# altair_sch.net
KiCad netlist of a schematic drawn in EAGLE
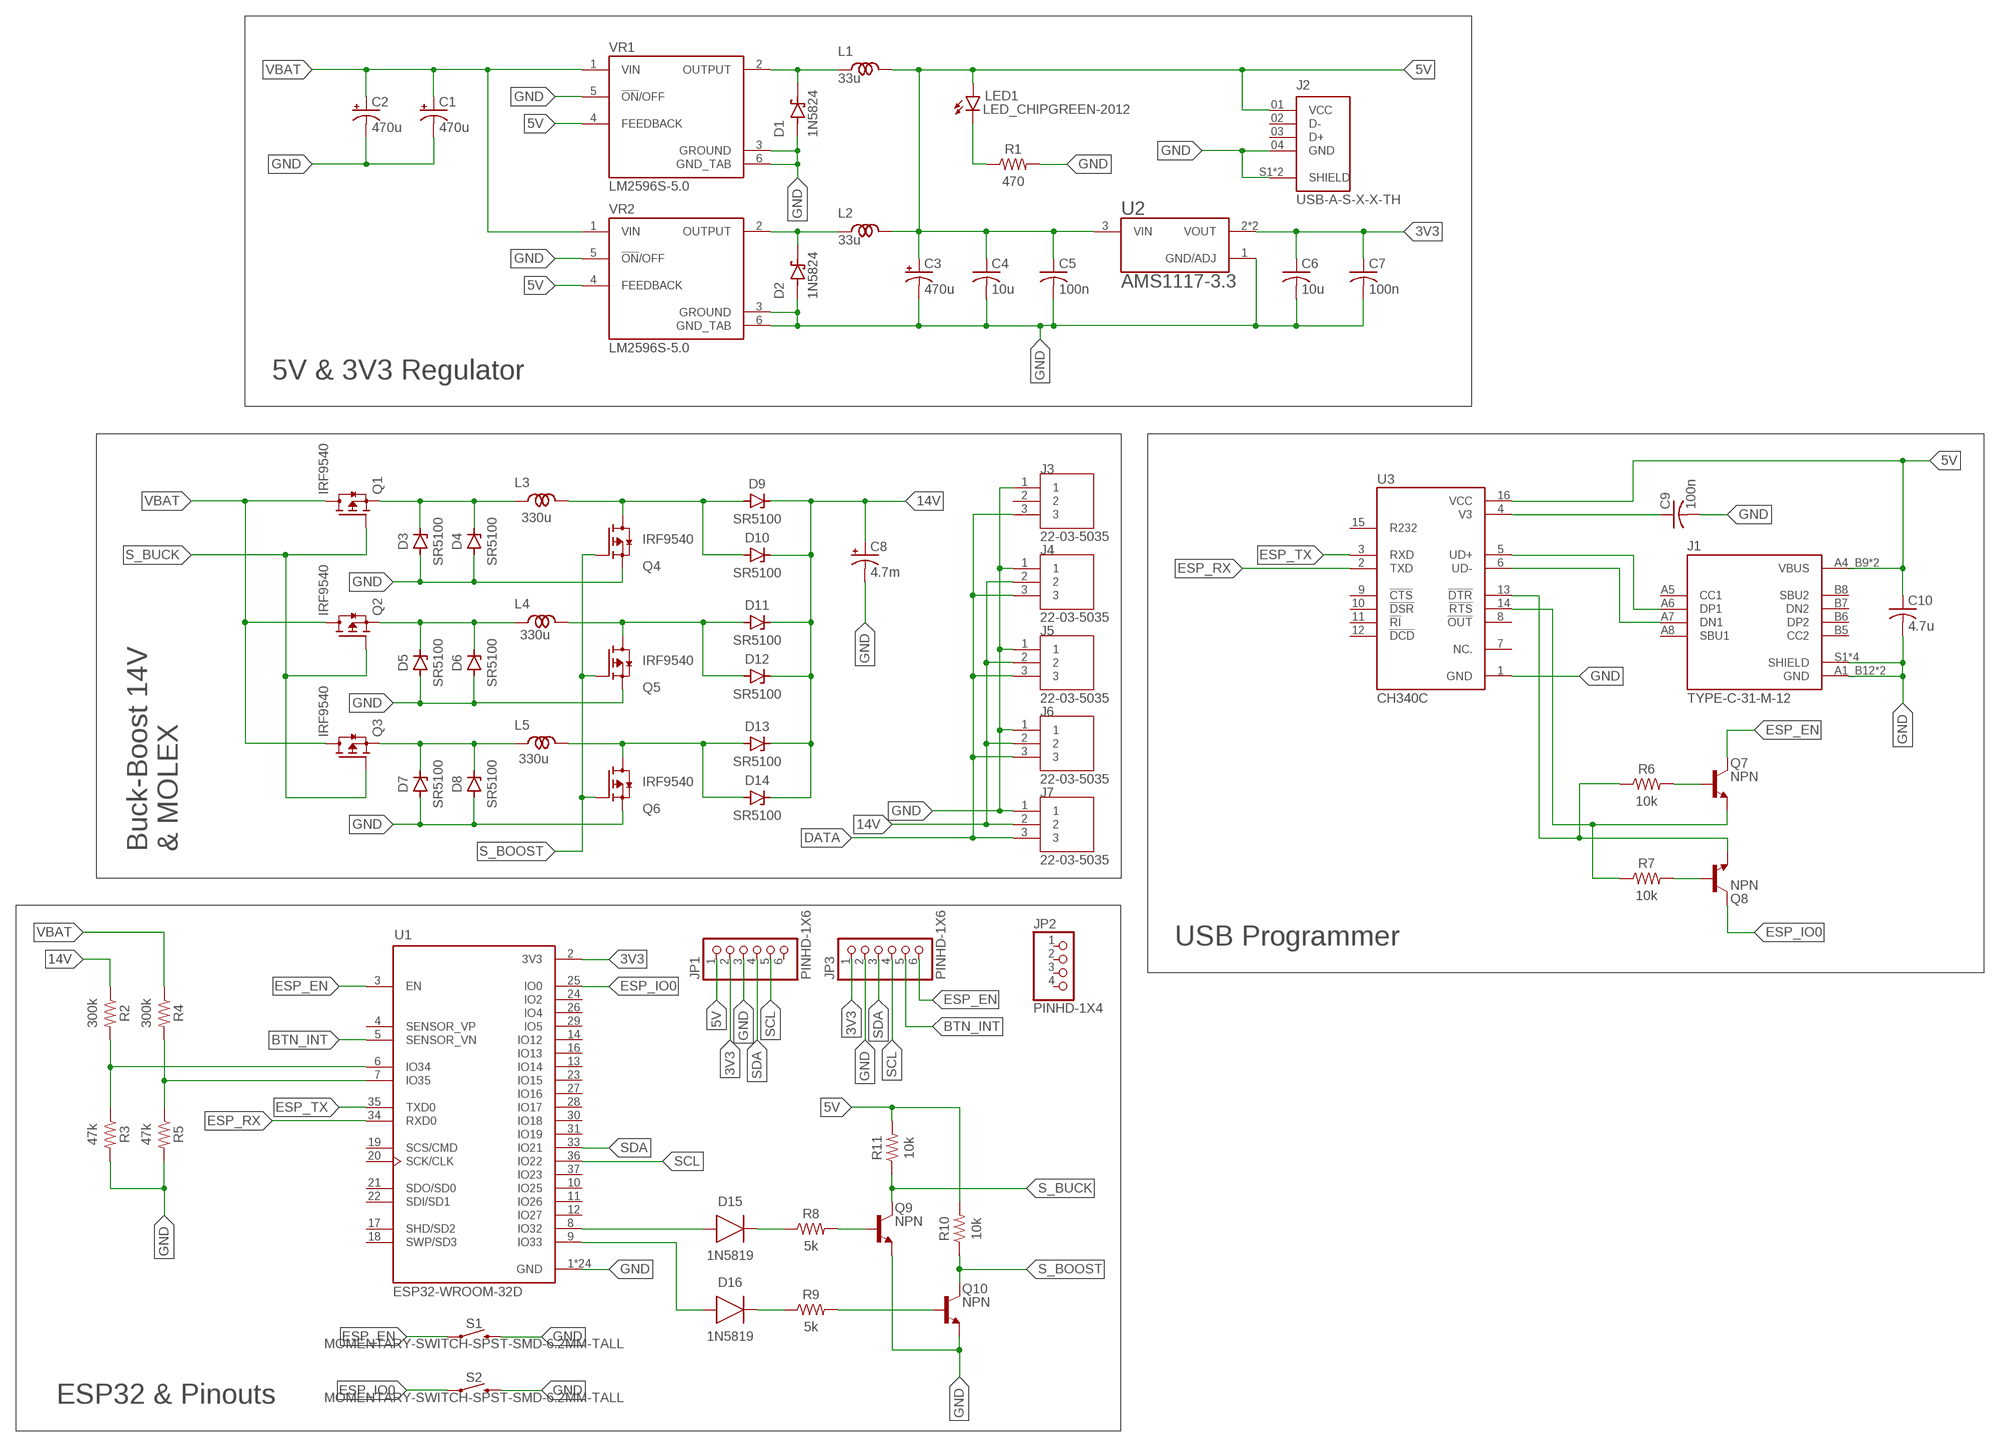
[diagram p0: schematic, sheet 1]

(export (version "E")
  (design (tool "Eeschema 10.0.6"))
  (components
    (comp (ref "C1")
      (value "470u")
      (footprint "eagle-import:CAPAE1030X1050N")
      (libsource (lib "eagle-import") (part "C-POL-USECAP-10.5MM_"))
    )
    (comp (ref "C2")
      (value "470u")
      (footprint "eagle-import:CAPAE1030X1050N")
      (libsource (lib "eagle-import") (part "C-POL-USECAP-10.5MM_"))
    )
    (comp (ref "C3")
      (value "470u")
      (footprint "eagle-import:CAPAE1030X1050N")
      (libsource (lib "eagle-import") (part "C-POL-USECAP-10.5MM_"))
    )
    (comp (ref "C4")
      (value "10u")
      (footprint "eagle-import:CAPC2012X110")
      (libsource (lib "eagle-import") (part "C-USCHIP-0805(2012-METRIC)_"))
    )
    (comp (ref "C5")
      (value "100n")
      (footprint "eagle-import:CAPC2012X110")
      (libsource (lib "eagle-import") (part "C-USCHIP-0805(2012-METRIC)_"))
    )
    (comp (ref "C6")
      (value "10u")
      (footprint "eagle-import:CAPC2012X110")
      (libsource (lib "eagle-import") (part "C-USCHIP-0805(2012-METRIC)_"))
    )
    (comp (ref "C7")
      (value "100n")
      (footprint "eagle-import:CAPC2012X110")
      (libsource (lib "eagle-import") (part "C-USCHIP-0805(2012-METRIC)_"))
    )
    (comp (ref "C8")
      (value "4.7m")
      (footprint "eagle-import:CAPPRD550W60D1200H2000B")
      (libsource (lib "eagle-import") (part "C-POL-USRADIAL-20MM-DIA_"))
    )
    (comp (ref "C9")
      (value "100n")
      (footprint "eagle-import:CAPC2012X110")
      (libsource (lib "eagle-import") (part "C-USCHIP-0805(2012-METRIC)_"))
    )
    (comp (ref "C10")
      (value "4.7u")
      (footprint "eagle-import:CAPC2012X110")
      (libsource (lib "eagle-import") (part "C-USCHIP-0805(2012-METRIC)_"))
    )
    (comp (ref "D1")
      (value "1N5824")
      (footprint "eagle-import:SODFL4725X110N")
      (fields (field (name "MF") "Taiwan Semiconductor") (field (name "MP") "SS54FSH"))
      (libsource (lib "eagle-import") (part "SS54FSH"))
    )
    (comp (ref "D2")
      (value "1N5824")
      (footprint "eagle-import:SODFL4725X110N")
      (fields (field (name "MF") "Taiwan Semiconductor") (field (name "MP") "SS54FSH"))
      (libsource (lib "eagle-import") (part "SS54FSH"))
    )
    (comp (ref "D3")
      (value "SR5100")
      (footprint "eagle-import:DIOM5226X290N")
      (libsource (lib "eagle-import") (part "ZENERDO-214AC(SMA)"))
    )
    (comp (ref "D4")
      (value "SR5100")
      (footprint "eagle-import:DIOM5226X290N")
      (libsource (lib "eagle-import") (part "ZENERDO-214AC(SMA)"))
    )
    (comp (ref "D5")
      (value "SR5100")
      (footprint "eagle-import:DIOM5226X290N")
      (libsource (lib "eagle-import") (part "ZENERDO-214AC(SMA)"))
    )
    (comp (ref "D6")
      (value "SR5100")
      (footprint "eagle-import:DIOM5226X290N")
      (libsource (lib "eagle-import") (part "ZENERDO-214AC(SMA)"))
    )
    (comp (ref "D7")
      (value "SR5100")
      (footprint "eagle-import:DIOM5226X290N")
      (libsource (lib "eagle-import") (part "ZENERDO-214AC(SMA)"))
    )
    (comp (ref "D8")
      (value "SR5100")
      (footprint "eagle-import:DIOM5226X290N")
      (libsource (lib "eagle-import") (part "ZENERDO-214AC(SMA)"))
    )
    (comp (ref "D9")
      (value "SR5100")
      (footprint "eagle-import:DIOM5226X290N")
      (libsource (lib "eagle-import") (part "ZENERDO-214AC(SMA)"))
    )
    (comp (ref "D10")
      (value "SR5100")
      (footprint "eagle-import:DIOM5226X290N")
      (libsource (lib "eagle-import") (part "ZENERDO-214AC(SMA)"))
    )
    (comp (ref "D11")
      (value "SR5100")
      (footprint "eagle-import:DIOM5226X290N")
      (libsource (lib "eagle-import") (part "ZENERDO-214AC(SMA)"))
    )
    (comp (ref "D12")
      (value "SR5100")
      (footprint "eagle-import:DIOM5226X290N")
      (libsource (lib "eagle-import") (part "ZENERDO-214AC(SMA)"))
    )
    (comp (ref "D13")
      (value "SR5100")
      (footprint "eagle-import:DIOM5226X290N")
      (libsource (lib "eagle-import") (part "ZENERDO-214AC(SMA)"))
    )
    (comp (ref "D14")
      (value "SR5100")
      (footprint "eagle-import:DIOM5226X290N")
      (libsource (lib "eagle-import") (part "ZENERDO-214AC(SMA)"))
    )
    (comp (ref "D15")
      (value "1N5819")
      (footprint "eagle-import:DIOM5226X290N")
      (libsource (lib "eagle-import") (part "DIODEDO-214AC(SMA)"))
    )
    (comp (ref "D16")
      (value "1N5819")
      (footprint "eagle-import:DIOM5226X290N")
      (libsource (lib "eagle-import") (part "DIODEDO-214AC(SMA)"))
    )
    (comp (ref "J1")
      (value "TYPE-C-31-M-12")
      (footprint "eagle-import:HRO_TYPE-C-31-M-12")
      (fields (field (name "MF") "HRO Electronics Co., Ltd."))
      (libsource (lib "eagle-import") (part "TYPE-C-31-M-12"))
    )
    (comp (ref "J2")
      (value "USB-A-S-X-X-TH")
      (footprint "eagle-import:SAMTEC_USB-A-S-X-X-TH")
      (fields (field (name "MF") "Samtec") (field (name "MP") "USB-A-S-S-W-TH"))
      (libsource (lib "eagle-import") (part "USB-A-S-X-X-TH"))
    )
    (comp (ref "J3")
      (value "22-03-5035")
      (footprint "eagle-import:MOLEX_22-03-5035")
      (fields (field (name "MF") "Molex"))
      (libsource (lib "eagle-import") (part "22-03-5035"))
    )
    (comp (ref "J4")
      (value "22-03-5035")
      (footprint "eagle-import:MOLEX_22-03-5035")
      (fields (field (name "MF") "Molex"))
      (libsource (lib "eagle-import") (part "22-03-5035"))
    )
    (comp (ref "J5")
      (value "22-03-5035")
      (footprint "eagle-import:MOLEX_22-03-5035")
      (fields (field (name "MF") "Molex"))
      (libsource (lib "eagle-import") (part "22-03-5035"))
    )
    (comp (ref "J6")
      (value "22-03-5035")
      (footprint "eagle-import:MOLEX_22-03-5035")
      (fields (field (name "MF") "Molex"))
      (libsource (lib "eagle-import") (part "22-03-5035"))
    )
    (comp (ref "J7")
      (value "22-03-5035")
      (footprint "eagle-import:MOLEX_22-03-5035")
      (fields (field (name "MF") "Molex"))
      (libsource (lib "eagle-import") (part "22-03-5035"))
    )
    (comp (ref "JP1")
      (value "PINHD-1X6")
      (footprint "eagle-import:1X06")
      (fields (field (name "MANUFACTURER") "Generic"))
      (libsource (lib "eagle-import") (part "PINHD-1X6"))
    )
    (comp (ref "JP2")
      (value "PINHD-1X4")
      (footprint "eagle-import:1X04")
      (fields (field (name "MANUFACTURER") "Generic"))
      (libsource (lib "eagle-import") (part "PINHD-1X4"))
    )
    (comp (ref "JP3")
      (value "PINHD-1X6")
      (footprint "eagle-import:1X06")
      (fields (field (name "MANUFACTURER") "Generic"))
      (libsource (lib "eagle-import") (part "PINHD-1X6"))
    )
    (comp (ref "L1")
      (value "33u")
      (footprint "eagle-import:CDRH127R")
      (libsource (lib "eagle-import") (part "CDRH127R"))
    )
    (comp (ref "L2")
      (value "33u")
      (footprint "eagle-import:CDRH127R")
      (libsource (lib "eagle-import") (part "CDRH127R"))
    )
    (comp (ref "L3")
      (value "330u")
      (footprint "eagle-import:CDRH127R")
      (libsource (lib "eagle-import") (part "CDRH127R"))
    )
    (comp (ref "L4")
      (value "330u")
      (footprint "eagle-import:CDRH127R")
      (libsource (lib "eagle-import") (part "CDRH127R"))
    )
    (comp (ref "L5")
      (value "330u")
      (footprint "eagle-import:CDRH127R")
      (libsource (lib "eagle-import") (part "CDRH127R"))
    )
    (comp (ref "LED1")
      (value "LED_CHIPGREEN-2012")
      (footprint "eagle-import:LEDC2012X110N_G")
      (libsource (lib "eagle-import") (part "LED_CHIPGREEN-2012"))
    )
    (comp (ref "Q1")
      (value "IRF9540")
      (footprint "eagle-import:TO254P1052X465X1989-3")
      (fields (field (name "MF") "Vishay Siliconix"))
      (libsource (lib "eagle-import") (part "IRF9540"))
    )
    (comp (ref "Q2")
      (value "IRF9540")
      (footprint "eagle-import:TO254P1052X465X1989-3")
      (fields (field (name "MF") "Vishay Siliconix"))
      (libsource (lib "eagle-import") (part "IRF9540"))
    )
    (comp (ref "Q3")
      (value "IRF9540")
      (footprint "eagle-import:TO254P1052X465X1989-3")
      (fields (field (name "MF") "Vishay Siliconix"))
      (libsource (lib "eagle-import") (part "IRF9540"))
    )
    (comp (ref "Q4")
      (value "IRF9540")
      (footprint "eagle-import:TO254P1052X465X1989-3")
      (fields (field (name "MF") "Vishay Siliconix"))
      (libsource (lib "eagle-import") (part "IRF9540"))
    )
    (comp (ref "Q5")
      (value "IRF9540")
      (footprint "eagle-import:TO254P1052X465X1989-3")
      (fields (field (name "MF") "Vishay Siliconix"))
      (libsource (lib "eagle-import") (part "IRF9540"))
    )
    (comp (ref "Q6")
      (value "IRF9540")
      (footprint "eagle-import:TO254P1052X465X1989-3")
      (fields (field (name "MF") "Vishay Siliconix"))
      (libsource (lib "eagle-import") (part "IRF9540"))
    )
    (comp (ref "Q7")
      (value "NPN")
      (footprint "eagle-import:SOT95P237X112-3N")
      (libsource (lib "eagle-import") (part "NPNSOT23-BEC_"))
    )
    (comp (ref "Q8")
      (value "NPN")
      (footprint "eagle-import:SOT95P237X112-3N")
      (libsource (lib "eagle-import") (part "NPNSOT23-BEC_"))
    )
    (comp (ref "Q9")
      (value "NPN")
      (footprint "eagle-import:SOT95P237X112-3N")
      (libsource (lib "eagle-import") (part "NPNSOT23-BEC_"))
    )
    (comp (ref "Q10")
      (value "NPN")
      (footprint "eagle-import:SOT95P237X112-3N")
      (libsource (lib "eagle-import") (part "NPNSOT23-BEC_"))
    )
    (comp (ref "R1")
      (value "470")
      (footprint "eagle-import:RESC2012X65")
      (libsource (lib "eagle-import") (part "R-USCHIP-0805(2012-METRIC)_"))
    )
    (comp (ref "R2")
      (value "300k")
      (footprint "eagle-import:RESC2012X65")
      (libsource (lib "eagle-import") (part "R-USCHIP-0805(2012-METRIC)_"))
    )
    (comp (ref "R3")
      (value "47k")
      (footprint "eagle-import:RESC2012X65")
      (libsource (lib "eagle-import") (part "R-USCHIP-0805(2012-METRIC)_"))
    )
    (comp (ref "R4")
      (value "300k")
      (footprint "eagle-import:RESC2012X65")
      (libsource (lib "eagle-import") (part "R-USCHIP-0805(2012-METRIC)_"))
    )
    (comp (ref "R5")
      (value "47k")
      (footprint "eagle-import:RESC2012X65")
      (libsource (lib "eagle-import") (part "R-USCHIP-0805(2012-METRIC)_"))
    )
    (comp (ref "R6")
      (value "10k")
      (footprint "eagle-import:RESC2012X65")
      (libsource (lib "eagle-import") (part "R-USCHIP-0805(2012-METRIC)_"))
    )
    (comp (ref "R7")
      (value "10k")
      (footprint "eagle-import:RESC2012X65")
      (libsource (lib "eagle-import") (part "R-USCHIP-0805(2012-METRIC)_"))
    )
    (comp (ref "R8")
      (value "5k")
      (footprint "eagle-import:RESC2012X65")
      (libsource (lib "eagle-import") (part "R-USCHIP-0805(2012-METRIC)_"))
    )
    (comp (ref "R9")
      (value "5k")
      (footprint "eagle-import:RESC2012X65")
      (libsource (lib "eagle-import") (part "R-USCHIP-0805(2012-METRIC)_"))
    )
    (comp (ref "R10")
      (value "10k")
      (footprint "eagle-import:RESC2012X65")
      (libsource (lib "eagle-import") (part "R-USCHIP-0805(2012-METRIC)_"))
    )
    (comp (ref "R11")
      (value "10k")
      (footprint "eagle-import:RESC2012X65")
      (libsource (lib "eagle-import") (part "R-USCHIP-0805(2012-METRIC)_"))
    )
    (comp (ref "S1")
      (value "MOMENTARY-SWITCH-SPST-SMD-6.2MM-TALL")
      (footprint "eagle-import:TACTILE_SWITCH_SMD_6.2MM_TALL")
      (libsource (lib "eagle-import") (part "MOMENTARY-SWITCH-SPST-SMD-6.2MM-TALL"))
    )
    (comp (ref "S2")
      (value "MOMENTARY-SWITCH-SPST-SMD-6.2MM-TALL")
      (footprint "eagle-import:TACTILE_SWITCH_SMD_6.2MM_TALL")
      (libsource (lib "eagle-import") (part "MOMENTARY-SWITCH-SPST-SMD-6.2MM-TALL"))
    )
    (comp (ref "U1")
      (value "ESP32-WROOM-32D")
      (footprint "eagle-import:MODULE_ESP32-WROOM-32D")
      (fields (field (name "MF") "Espressif Systems"))
      (libsource (lib "eagle-import") (part "ESP32-WROOM-32D"))
    )
    (comp (ref "U2")
      (value "AMS1117-3.3")
      (footprint "eagle-import:SOT229P700X180-4N")
      (fields (field (name "MF") "Advanced Monolithic Systems"))
      (libsource (lib "eagle-import") (part "AMS1117-3.3"))
    )
    (comp (ref "U3")
      (value "CH340C")
      (footprint "eagle-import:SOIC127P600X180-16N")
      (fields (field (name "MF") "WCH"))
      (libsource (lib "eagle-import") (part "CH340C"))
    )
    (comp (ref "VR1")
      (value "LM2596S-5.0")
      (footprint "eagle-import:TO170P1524X483-6N")
      (fields (field (name "MF") "Texas Instruments") (field (name "MP") "LM2596S-5.0/NOPB"))
      (libsource (lib "eagle-import") (part "LM2596S-5.0"))
    )
    (comp (ref "VR2")
      (value "LM2596S-5.0")
      (footprint "eagle-import:TO170P1524X483-6N")
      (fields (field (name "MF") "Texas Instruments") (field (name "MP") "LM2596S-5.0/NOPB"))
      (libsource (lib "eagle-import") (part "LM2596S-5.0"))
    )
  )
  (nets
    (net (code "1") (name "3V3") (class "Default")
      (node (ref "C6") (pin "1") (pinfunction "1_1") (pintype "passive"))
      (node (ref "C7") (pin "1") (pinfunction "1_1") (pintype "passive"))
      (node (ref "JP1") (pin "2") (pinfunction "2_2") (pintype "passive"))
      (node (ref "JP3") (pin "1") (pinfunction "1_1") (pintype "passive"))
      (node (ref "U1") (pin "2") (pinfunction "3V3_2") (pintype "power_in"))
      (node (ref "U2") (pin "2") (pinfunction "VOUT_2") (pintype "output"))
      (node (ref "U2") (pin "4") (pinfunction "VOUT_4") (pintype "output"))
    )
    (net (code "2") (name "5V") (class "Default")
      (node (ref "C10") (pin "1") (pinfunction "1_1") (pintype "passive"))
      (node (ref "C3") (pin "1") (pinfunction "+_1") (pintype "passive"))
      (node (ref "C4") (pin "1") (pinfunction "1_1") (pintype "passive"))
      (node (ref "C5") (pin "1") (pinfunction "1_1") (pintype "passive"))
      (node (ref "J1") (pin "A4_B9") (pinfunction "VBUS_A4_B9") (pintype "power_in"))
      (node (ref "J1") (pin "B4_A9") (pinfunction "VBUS_B4_A9") (pintype "power_in"))
      (node (ref "J2") (pin "01") (pinfunction "VCC_01") (pintype "power_in"))
      (node (ref "JP1") (pin "1") (pinfunction "1_1") (pintype "passive"))
      (node (ref "L1") (pin "P$2") (pinfunction "P$2_P$2") (pintype "bidirectional"))
      (node (ref "L2") (pin "P$2") (pinfunction "P$2_P$2") (pintype "bidirectional"))
      (node (ref "LED1") (pin "2") (pinfunction "A_2") (pintype "passive"))
      (node (ref "R10") (pin "2") (pinfunction "2_2") (pintype "passive"))
      (node (ref "R11") (pin "2") (pinfunction "2_2") (pintype "passive"))
      (node (ref "U2") (pin "3") (pinfunction "VIN_3") (pintype "input"))
      (node (ref "U3") (pin "16") (pinfunction "VCC_16") (pintype "power_in"))
      (node (ref "VR1") (pin "4") (pinfunction "FEEDBACK_4") (pintype "input"))
      (node (ref "VR2") (pin "4") (pinfunction "FEEDBACK_4") (pintype "input"))
    )
    (net (code "3") (name "14V") (class "Default")
      (node (ref "C8") (pin "1") (pinfunction "+_1") (pintype "passive"))
      (node (ref "D10") (pin "1") (pinfunction "C_1") (pintype "passive"))
      (node (ref "D11") (pin "1") (pinfunction "C_1") (pintype "passive"))
      (node (ref "D12") (pin "1") (pinfunction "C_1") (pintype "passive"))
      (node (ref "D13") (pin "1") (pinfunction "C_1") (pintype "passive"))
      (node (ref "D14") (pin "1") (pinfunction "C_1") (pintype "passive"))
      (node (ref "D9") (pin "1") (pinfunction "C_1") (pintype "passive"))
      (node (ref "J4") (pin "2") (pinfunction "2_2") (pintype "passive"))
      (node (ref "J5") (pin "2") (pinfunction "2_2") (pintype "passive"))
      (node (ref "J6") (pin "2") (pinfunction "2_2") (pintype "passive"))
      (node (ref "J7") (pin "2") (pinfunction "2_2") (pintype "passive"))
      (node (ref "R2") (pin "1") (pinfunction "1_1") (pintype "passive"))
    )
    (net (code "4") (name "BTN_INT") (class "Default")
      (node (ref "JP3") (pin "5") (pinfunction "5_5") (pintype "passive"))
      (node (ref "U1") (pin "5") (pinfunction "SENSOR_VN_5") (pintype "input"))
    )
    (net (code "5") (name "DATA") (class "Default")
      (node (ref "J3") (pin "3") (pinfunction "3_3") (pintype "passive"))
      (node (ref "J4") (pin "3") (pinfunction "3_3") (pintype "passive"))
      (node (ref "J5") (pin "3") (pinfunction "3_3") (pintype "passive"))
      (node (ref "J6") (pin "3") (pinfunction "3_3") (pintype "passive"))
      (node (ref "J7") (pin "3") (pinfunction "3_3") (pintype "passive"))
    )
    (net (code "6") (name "ESP_EN") (class "Default")
      (node (ref "JP3") (pin "6") (pinfunction "6_6") (pintype "passive"))
      (node (ref "Q7") (pin "3") (pinfunction "C_3") (pintype "passive"))
      (node (ref "S1") (pin "A2") (pinfunction "1_A2") (pintype "passive"))
      (node (ref "U1") (pin "3") (pinfunction "EN_3") (pintype "input"))
    )
    (net (code "7") (name "ESP_IO0") (class "Default")
      (node (ref "Q8") (pin "3") (pinfunction "C_3") (pintype "passive"))
      (node (ref "S2") (pin "A2") (pinfunction "1_A2") (pintype "passive"))
      (node (ref "U1") (pin "25") (pinfunction "IO0_25") (pintype "bidirectional"))
    )
    (net (code "8") (name "ESP_RX") (class "Default")
      (node (ref "U1") (pin "34") (pinfunction "RXD0_34") (pintype "bidirectional"))
      (node (ref "U3") (pin "2") (pinfunction "TXD_2") (pintype "output"))
    )
    (net (code "9") (name "ESP_TX") (class "Default")
      (node (ref "U1") (pin "35") (pinfunction "TXD0_35") (pintype "bidirectional"))
      (node (ref "U3") (pin "3") (pinfunction "RXD_3") (pintype "input"))
    )
    (net (code "10") (name "GND") (class "Default")
      (node (ref "C1") (pin "2") (pinfunction "-_2") (pintype "passive"))
      (node (ref "C10") (pin "2") (pinfunction "2_2") (pintype "passive"))
      (node (ref "C2") (pin "2") (pinfunction "-_2") (pintype "passive"))
      (node (ref "C3") (pin "2") (pinfunction "-_2") (pintype "passive"))
      (node (ref "C4") (pin "2") (pinfunction "2_2") (pintype "passive"))
      (node (ref "C5") (pin "2") (pinfunction "2_2") (pintype "passive"))
      (node (ref "C6") (pin "2") (pinfunction "2_2") (pintype "passive"))
      (node (ref "C7") (pin "2") (pinfunction "2_2") (pintype "passive"))
      (node (ref "C8") (pin "2") (pinfunction "-_2") (pintype "passive"))
      (node (ref "C9") (pin "2") (pinfunction "2_2") (pintype "passive"))
      (node (ref "D1") (pin "A") (pinfunction "A_A") (pintype "passive"))
      (node (ref "D2") (pin "A") (pinfunction "A_A") (pintype "passive"))
      (node (ref "D3") (pin "2") (pinfunction "A_2") (pintype "passive"))
      (node (ref "D4") (pin "2") (pinfunction "A_2") (pintype "passive"))
      (node (ref "D5") (pin "2") (pinfunction "A_2") (pintype "passive"))
      (node (ref "D6") (pin "2") (pinfunction "A_2") (pintype "passive"))
      (node (ref "D7") (pin "2") (pinfunction "A_2") (pintype "passive"))
      (node (ref "D8") (pin "2") (pinfunction "A_2") (pintype "passive"))
      (node (ref "J1") (pin "A1_B12") (pinfunction "GND_A1_B12") (pintype "power_in"))
      (node (ref "J1") (pin "B1_A12") (pinfunction "GND_B1_A12") (pintype "power_in"))
      (node (ref "J1") (pin "S1") (pinfunction "SHIELD_S1") (pintype "passive"))
      (node (ref "J1") (pin "S2") (pinfunction "SHIELD_S2") (pintype "passive"))
      (node (ref "J1") (pin "S3") (pinfunction "SHIELD_S3") (pintype "passive"))
      (node (ref "J1") (pin "S4") (pinfunction "SHIELD_S4") (pintype "passive"))
      (node (ref "J2") (pin "04") (pinfunction "GND_04") (pintype "power_in"))
      (node (ref "J2") (pin "S1") (pinfunction "SHIELD_S1") (pintype "passive"))
      (node (ref "J2") (pin "S2") (pinfunction "SHIELD_S2") (pintype "passive"))
      (node (ref "J3") (pin "1") (pinfunction "1_1") (pintype "passive"))
      (node (ref "J4") (pin "1") (pinfunction "1_1") (pintype "passive"))
      (node (ref "J5") (pin "1") (pinfunction "1_1") (pintype "passive"))
      (node (ref "J6") (pin "1") (pinfunction "1_1") (pintype "passive"))
      (node (ref "J7") (pin "1") (pinfunction "1_1") (pintype "passive"))
      (node (ref "JP1") (pin "3") (pinfunction "3_3") (pintype "passive"))
      (node (ref "JP3") (pin "2") (pinfunction "2_2") (pintype "passive"))
      (node (ref "Q10") (pin "2") (pinfunction "E_2") (pintype "passive"))
      (node (ref "Q4") (pin "3") (pinfunction "S_3") (pintype "passive"))
      (node (ref "Q5") (pin "3") (pinfunction "S_3") (pintype "passive"))
      (node (ref "Q6") (pin "3") (pinfunction "S_3") (pintype "passive"))
      (node (ref "Q9") (pin "2") (pinfunction "E_2") (pintype "passive"))
      (node (ref "R1") (pin "2") (pinfunction "2_2") (pintype "passive"))
      (node (ref "R3") (pin "2") (pinfunction "2_2") (pintype "passive"))
      (node (ref "R5") (pin "2") (pinfunction "2_2") (pintype "passive"))
      (node (ref "S1") (pin "B2") (pinfunction "2_B2") (pintype "passive"))
      (node (ref "S2") (pin "B2") (pinfunction "2_B2") (pintype "passive"))
      (node (ref "U1") (pin "1") (pinfunction "GND_1") (pintype "power_in"))
      (node (ref "U1") (pin "15") (pinfunction "GND_15") (pintype "power_in"))
      (node (ref "U1") (pin "38") (pinfunction "GND_38") (pintype "power_in"))
      (node (ref "U1") (pin "39_1") (pinfunction "GND_39_1") (pintype "power_in"))
      (node (ref "U1") (pin "39_10") (pinfunction "GND_39_10") (pintype "power_in"))
      (node (ref "U1") (pin "39_11") (pinfunction "GND_39_11") (pintype "power_in"))
      (node (ref "U1") (pin "39_12") (pinfunction "GND_39_12") (pintype "power_in"))
      (node (ref "U1") (pin "39_13") (pinfunction "GND_39_13") (pintype "power_in"))
      (node (ref "U1") (pin "39_14") (pinfunction "GND_39_14") (pintype "power_in"))
      (node (ref "U1") (pin "39_15") (pinfunction "GND_39_15") (pintype "power_in"))
      (node (ref "U1") (pin "39_16") (pinfunction "GND_39_16") (pintype "power_in"))
      (node (ref "U1") (pin "39_17") (pinfunction "GND_39_17") (pintype "power_in"))
      (node (ref "U1") (pin "39_18") (pinfunction "GND_39_18") (pintype "power_in"))
      (node (ref "U1") (pin "39_19") (pinfunction "GND_39_19") (pintype "power_in"))
      (node (ref "U1") (pin "39_2") (pinfunction "GND_39_2") (pintype "power_in"))
      (node (ref "U1") (pin "39_20") (pinfunction "GND_39_20") (pintype "power_in"))
      (node (ref "U1") (pin "39_21") (pinfunction "GND_39_21") (pintype "power_in"))
      (node (ref "U1") (pin "39_3") (pinfunction "GND_39_3") (pintype "power_in"))
      (node (ref "U1") (pin "39_4") (pinfunction "GND_39_4") (pintype "power_in"))
      (node (ref "U1") (pin "39_5") (pinfunction "GND_39_5") (pintype "power_in"))
      (node (ref "U1") (pin "39_6") (pinfunction "GND_39_6") (pintype "power_in"))
      (node (ref "U1") (pin "39_7") (pinfunction "GND_39_7") (pintype "power_in"))
      (node (ref "U1") (pin "39_8") (pinfunction "GND_39_8") (pintype "power_in"))
      (node (ref "U1") (pin "39_9") (pinfunction "GND_39_9") (pintype "power_in"))
      (node (ref "U2") (pin "1") (pinfunction "GND/ADJ_1") (pintype "power_in"))
      (node (ref "U3") (pin "1") (pinfunction "GND_1") (pintype "power_in"))
      (node (ref "VR1") (pin "3") (pinfunction "GROUND_3") (pintype "power_in"))
      (node (ref "VR1") (pin "5") (pinfunction "~{ON}/OFF_5") (pintype "input"))
      (node (ref "VR1") (pin "6") (pinfunction "GND_TAB_6") (pintype "power_in"))
      (node (ref "VR2") (pin "3") (pinfunction "GROUND_3") (pintype "power_in"))
      (node (ref "VR2") (pin "5") (pinfunction "~{ON}/OFF_5") (pintype "input"))
      (node (ref "VR2") (pin "6") (pinfunction "GND_TAB_6") (pintype "power_in"))
    )
    (net (code "11") (name "Net-(D1-K)") (class "Default")
      (node (ref "D1") (pin "C") (pinfunction "K_C") (pintype "passive"))
      (node (ref "L1") (pin "P$1") (pinfunction "P$1_P$1") (pintype "bidirectional"))
      (node (ref "VR1") (pin "2") (pinfunction "OUTPUT_2") (pintype "output"))
    )
    (net (code "12") (name "Net-(D2-K)") (class "Default")
      (node (ref "D2") (pin "C") (pinfunction "K_C") (pintype "passive"))
      (node (ref "L2") (pin "P$1") (pinfunction "P$1_P$1") (pintype "bidirectional"))
      (node (ref "VR2") (pin "2") (pinfunction "OUTPUT_2") (pintype "output"))
    )
    (net (code "13") (name "Net-(D3-C)") (class "Default")
      (node (ref "D3") (pin "1") (pinfunction "C_1") (pintype "passive"))
      (node (ref "D4") (pin "1") (pinfunction "C_1") (pintype "passive"))
      (node (ref "L3") (pin "P$1") (pinfunction "P$1_P$1") (pintype "bidirectional"))
      (node (ref "Q1") (pin "3") (pinfunction "S_3") (pintype "passive"))
    )
    (net (code "14") (name "Net-(D5-C)") (class "Default")
      (node (ref "D5") (pin "1") (pinfunction "C_1") (pintype "passive"))
      (node (ref "D6") (pin "1") (pinfunction "C_1") (pintype "passive"))
      (node (ref "L4") (pin "P$1") (pinfunction "P$1_P$1") (pintype "bidirectional"))
      (node (ref "Q2") (pin "3") (pinfunction "S_3") (pintype "passive"))
    )
    (net (code "15") (name "Net-(D7-C)") (class "Default")
      (node (ref "D7") (pin "1") (pinfunction "C_1") (pintype "passive"))
      (node (ref "D8") (pin "1") (pinfunction "C_1") (pintype "passive"))
      (node (ref "L5") (pin "P$1") (pinfunction "P$1_P$1") (pintype "bidirectional"))
      (node (ref "Q3") (pin "3") (pinfunction "S_3") (pintype "passive"))
    )
    (net (code "16") (name "Net-(D10-A)") (class "Default")
      (node (ref "D10") (pin "2") (pinfunction "A_2") (pintype "passive"))
      (node (ref "D9") (pin "2") (pinfunction "A_2") (pintype "passive"))
      (node (ref "L3") (pin "P$2") (pinfunction "P$2_P$2") (pintype "bidirectional"))
      (node (ref "Q4") (pin "2") (pinfunction "D_2") (pintype "passive"))
    )
    (net (code "17") (name "Net-(D11-A)") (class "Default")
      (node (ref "D11") (pin "2") (pinfunction "A_2") (pintype "passive"))
      (node (ref "D12") (pin "2") (pinfunction "A_2") (pintype "passive"))
      (node (ref "L4") (pin "P$2") (pinfunction "P$2_P$2") (pintype "bidirectional"))
      (node (ref "Q5") (pin "2") (pinfunction "D_2") (pintype "passive"))
    )
    (net (code "18") (name "Net-(D13-A)") (class "Default")
      (node (ref "D13") (pin "2") (pinfunction "A_2") (pintype "passive"))
      (node (ref "D14") (pin "2") (pinfunction "A_2") (pintype "passive"))
      (node (ref "L5") (pin "P$2") (pinfunction "P$2_P$2") (pintype "bidirectional"))
      (node (ref "Q6") (pin "2") (pinfunction "D_2") (pintype "passive"))
    )
    (net (code "19") (name "Net-(D15-A)") (class "Default")
      (node (ref "D15") (pin "2") (pinfunction "A_2") (pintype "passive"))
      (node (ref "U1") (pin "8") (pinfunction "IO32_8") (pintype "bidirectional"))
    )
    (net (code "20") (name "Net-(D15-C)") (class "Default")
      (node (ref "D15") (pin "1") (pinfunction "C_1") (pintype "passive"))
      (node (ref "R8") (pin "1") (pinfunction "1_1") (pintype "passive"))
    )
    (net (code "21") (name "Net-(D16-A)") (class "Default")
      (node (ref "D16") (pin "2") (pinfunction "A_2") (pintype "passive"))
      (node (ref "U1") (pin "9") (pinfunction "IO33_9") (pintype "bidirectional"))
    )
    (net (code "22") (name "Net-(D16-C)") (class "Default")
      (node (ref "D16") (pin "1") (pinfunction "C_1") (pintype "passive"))
      (node (ref "R9") (pin "1") (pinfunction "1_1") (pintype "passive"))
    )
    (net (code "23") (name "Net-(J1-DN1)") (class "Default")
      (node (ref "J1") (pin "A7") (pinfunction "DN1_A7") (pintype "bidirectional"))
      (node (ref "U3") (pin "6") (pinfunction "UD-_6") (pintype "bidirectional"))
    )
    (net (code "24") (name "Net-(J1-DP1)") (class "Default")
      (node (ref "J1") (pin "A6") (pinfunction "DP1_A6") (pintype "bidirectional"))
      (node (ref "U3") (pin "5") (pinfunction "UD+_5") (pintype "bidirectional"))
    )
    (net (code "25") (name "Net-(LED1-C)") (class "Default")
      (node (ref "LED1") (pin "1") (pinfunction "C_1") (pintype "passive"))
      (node (ref "R1") (pin "1") (pinfunction "1_1") (pintype "passive"))
    )
    (net (code "26") (name "Net-(Q7-B)") (class "Default")
      (node (ref "Q7") (pin "1") (pinfunction "B_1") (pintype "passive"))
      (node (ref "R6") (pin "2") (pinfunction "2_2") (pintype "passive"))
    )
    (net (code "27") (name "Net-(Q7-E)") (class "Default")
      (node (ref "Q7") (pin "2") (pinfunction "E_2") (pintype "passive"))
      (node (ref "R7") (pin "1") (pinfunction "1_1") (pintype "passive"))
      (node (ref "U3") (pin "14") (pinfunction "~{RTS}_14") (pintype "output"))
    )
    (net (code "28") (name "Net-(Q8-B)") (class "Default")
      (node (ref "Q8") (pin "1") (pinfunction "B_1") (pintype "passive"))
      (node (ref "R7") (pin "2") (pinfunction "2_2") (pintype "passive"))
    )
    (net (code "29") (name "Net-(Q8-E)") (class "Default")
      (node (ref "Q8") (pin "2") (pinfunction "E_2") (pintype "passive"))
      (node (ref "R6") (pin "1") (pinfunction "1_1") (pintype "passive"))
      (node (ref "U3") (pin "13") (pinfunction "~{DTR}_13") (pintype "output"))
    )
    (net (code "30") (name "Net-(Q9-B)") (class "Default")
      (node (ref "Q9") (pin "1") (pinfunction "B_1") (pintype "passive"))
      (node (ref "R8") (pin "2") (pinfunction "2_2") (pintype "passive"))
    )
    (net (code "31") (name "Net-(Q10-B)") (class "Default")
      (node (ref "Q10") (pin "1") (pinfunction "B_1") (pintype "passive"))
      (node (ref "R9") (pin "2") (pinfunction "2_2") (pintype "passive"))
    )
    (net (code "32") (name "Net-(U1-IO34)") (class "Default")
      (node (ref "R2") (pin "2") (pinfunction "2_2") (pintype "passive"))
      (node (ref "R3") (pin "1") (pinfunction "1_1") (pintype "passive"))
      (node (ref "U1") (pin "6") (pinfunction "IO34_6") (pintype "input"))
    )
    (net (code "33") (name "Net-(U1-IO35)") (class "Default")
      (node (ref "R4") (pin "2") (pinfunction "2_2") (pintype "passive"))
      (node (ref "R5") (pin "1") (pinfunction "1_1") (pintype "passive"))
      (node (ref "U1") (pin "7") (pinfunction "IO35_7") (pintype "input"))
    )
    (net (code "34") (name "Net-(U3-V3)") (class "Default")
      (node (ref "C9") (pin "1") (pinfunction "1_1") (pintype "passive"))
      (node (ref "U3") (pin "4") (pinfunction "V3_4") (pintype "power_in"))
    )
    (net (code "35") (name "SCL") (class "Default")
      (node (ref "JP1") (pin "5") (pinfunction "5_5") (pintype "passive"))
      (node (ref "JP3") (pin "4") (pinfunction "4_4") (pintype "passive"))
      (node (ref "U1") (pin "36") (pinfunction "IO22_36") (pintype "bidirectional"))
    )
    (net (code "36") (name "SDA") (class "Default")
      (node (ref "JP1") (pin "4") (pinfunction "4_4") (pintype "passive"))
      (node (ref "JP3") (pin "3") (pinfunction "3_3") (pintype "passive"))
      (node (ref "U1") (pin "33") (pinfunction "IO21_33") (pintype "bidirectional"))
    )
    (net (code "37") (name "S_BOOST") (class "Default")
      (node (ref "Q10") (pin "3") (pinfunction "C_3") (pintype "passive"))
      (node (ref "Q4") (pin "1") (pinfunction "G_1") (pintype "passive"))
      (node (ref "Q5") (pin "1") (pinfunction "G_1") (pintype "passive"))
      (node (ref "Q6") (pin "1") (pinfunction "G_1") (pintype "passive"))
      (node (ref "R10") (pin "1") (pinfunction "1_1") (pintype "passive"))
    )
    (net (code "38") (name "S_BUCK") (class "Default")
      (node (ref "Q1") (pin "1") (pinfunction "G_1") (pintype "passive"))
      (node (ref "Q2") (pin "1") (pinfunction "G_1") (pintype "passive"))
      (node (ref "Q3") (pin "1") (pinfunction "G_1") (pintype "passive"))
      (node (ref "Q9") (pin "3") (pinfunction "C_3") (pintype "passive"))
      (node (ref "R11") (pin "1") (pinfunction "1_1") (pintype "passive"))
    )
    (net (code "39") (name "VBAT") (class "Default")
      (node (ref "C1") (pin "1") (pinfunction "+_1") (pintype "passive"))
      (node (ref "C2") (pin "1") (pinfunction "+_1") (pintype "passive"))
      (node (ref "Q1") (pin "2") (pinfunction "D_2") (pintype "passive"))
      (node (ref "Q2") (pin "2") (pinfunction "D_2") (pintype "passive"))
      (node (ref "Q3") (pin "2") (pinfunction "D_2") (pintype "passive"))
      (node (ref "R4") (pin "1") (pinfunction "1_1") (pintype "passive"))
      (node (ref "VR1") (pin "1") (pinfunction "VIN_1") (pintype "input"))
      (node (ref "VR2") (pin "1") (pinfunction "VIN_1") (pintype "input"))
    )
    (net (code "40") (name "unconnected-(J1-CC1-PadA5)") (class "Default")
      (node (ref "J1") (pin "A5") (pinfunction "CC1_A5") (pintype "bidirectional"))
    )
    (net (code "41") (name "unconnected-(J1-CC2-PadB5)") (class "Default")
      (node (ref "J1") (pin "B5") (pinfunction "CC2_B5") (pintype "bidirectional"))
    )
    (net (code "42") (name "unconnected-(J1-DN2-PadB7)") (class "Default")
      (node (ref "J1") (pin "B7") (pinfunction "DN2_B7") (pintype "bidirectional"))
    )
    (net (code "43") (name "unconnected-(J1-DP2-PadB6)") (class "Default")
      (node (ref "J1") (pin "B6") (pinfunction "DP2_B6") (pintype "bidirectional"))
    )
    (net (code "44") (name "unconnected-(J1-SBU1-PadA8)") (class "Default")
      (node (ref "J1") (pin "A8") (pinfunction "SBU1_A8") (pintype "bidirectional"))
    )
    (net (code "45") (name "unconnected-(J1-SBU2-PadB8)") (class "Default")
      (node (ref "J1") (pin "B8") (pinfunction "SBU2_B8") (pintype "bidirectional"))
    )
    (net (code "46") (name "unconnected-(J2-D+-Pad03)") (class "Default")
      (node (ref "J2") (pin "03") (pinfunction "D+_03") (pintype "bidirectional"))
    )
    (net (code "47") (name "unconnected-(J2-D--Pad02)") (class "Default")
      (node (ref "J2") (pin "02") (pinfunction "D-_02") (pintype "bidirectional"))
    )
    (net (code "48") (name "unconnected-(J3-Pad2)") (class "Default")
      (node (ref "J3") (pin "2") (pinfunction "2_2") (pintype "passive"))
    )
    (net (code "49") (name "unconnected-(JP1-Pad6)") (class "Default")
      (node (ref "JP1") (pin "6") (pinfunction "6_6") (pintype "passive"))
    )
    (net (code "50") (name "unconnected-(JP2-Pad1)") (class "Default")
      (node (ref "JP2") (pin "1") (pinfunction "1_1") (pintype "passive"))
    )
    (net (code "51") (name "unconnected-(JP2-Pad2)") (class "Default")
      (node (ref "JP2") (pin "2") (pinfunction "2_2") (pintype "passive"))
    )
    (net (code "52") (name "unconnected-(JP2-Pad3)") (class "Default")
      (node (ref "JP2") (pin "3") (pinfunction "3_3") (pintype "passive"))
    )
    (net (code "53") (name "unconnected-(JP2-Pad4)") (class "Default")
      (node (ref "JP2") (pin "4") (pinfunction "4_4") (pintype "passive"))
    )
    (net (code "54") (name "unconnected-(U1-IO2-Pad24)") (class "Default")
      (node (ref "U1") (pin "24") (pinfunction "IO2_24") (pintype "bidirectional"))
    )
    (net (code "55") (name "unconnected-(U1-IO4-Pad26)") (class "Default")
      (node (ref "U1") (pin "26") (pinfunction "IO4_26") (pintype "bidirectional"))
    )
    (net (code "56") (name "unconnected-(U1-IO5-Pad29)") (class "Default")
      (node (ref "U1") (pin "29") (pinfunction "IO5_29") (pintype "bidirectional"))
    )
    (net (code "57") (name "unconnected-(U1-IO12-Pad14)") (class "Default")
      (node (ref "U1") (pin "14") (pinfunction "IO12_14") (pintype "bidirectional"))
    )
    (net (code "58") (name "unconnected-(U1-IO13-Pad16)") (class "Default")
      (node (ref "U1") (pin "16") (pinfunction "IO13_16") (pintype "bidirectional"))
    )
    (net (code "59") (name "unconnected-(U1-IO14-Pad13)") (class "Default")
      (node (ref "U1") (pin "13") (pinfunction "IO14_13") (pintype "bidirectional"))
    )
    (net (code "60") (name "unconnected-(U1-IO15-Pad23)") (class "Default")
      (node (ref "U1") (pin "23") (pinfunction "IO15_23") (pintype "bidirectional"))
    )
    (net (code "61") (name "unconnected-(U1-IO16-Pad27)") (class "Default")
      (node (ref "U1") (pin "27") (pinfunction "IO16_27") (pintype "bidirectional"))
    )
    (net (code "62") (name "unconnected-(U1-IO17-Pad28)") (class "Default")
      (node (ref "U1") (pin "28") (pinfunction "IO17_28") (pintype "bidirectional"))
    )
    (net (code "63") (name "unconnected-(U1-IO18-Pad30)") (class "Default")
      (node (ref "U1") (pin "30") (pinfunction "IO18_30") (pintype "bidirectional"))
    )
    (net (code "64") (name "unconnected-(U1-IO19-Pad31)") (class "Default")
      (node (ref "U1") (pin "31") (pinfunction "IO19_31") (pintype "bidirectional"))
    )
    (net (code "65") (name "unconnected-(U1-IO23-Pad37)") (class "Default")
      (node (ref "U1") (pin "37") (pinfunction "IO23_37") (pintype "bidirectional"))
    )
    (net (code "66") (name "unconnected-(U1-IO25-Pad10)") (class "Default")
      (node (ref "U1") (pin "10") (pinfunction "IO25_10") (pintype "bidirectional"))
    )
    (net (code "67") (name "unconnected-(U1-IO26-Pad11)") (class "Default")
      (node (ref "U1") (pin "11") (pinfunction "IO26_11") (pintype "bidirectional"))
    )
    (net (code "68") (name "unconnected-(U1-IO27-Pad12)") (class "Default")
      (node (ref "U1") (pin "12") (pinfunction "IO27_12") (pintype "bidirectional"))
    )
    (net (code "69") (name "unconnected-(U1-SCK{slash}CLK-Pad20)") (class "Default")
      (node (ref "U1") (pin "20") (pinfunction "SCK/CLK_20") (pintype "bidirectional"))
    )
    (net (code "70") (name "unconnected-(U1-SCS{slash}CMD-Pad19)") (class "Default")
      (node (ref "U1") (pin "19") (pinfunction "SCS/CMD_19") (pintype "bidirectional"))
    )
    (net (code "71") (name "unconnected-(U1-SDI{slash}SD1-Pad22)") (class "Default")
      (node (ref "U1") (pin "22") (pinfunction "SDI/SD1_22") (pintype "bidirectional"))
    )
    (net (code "72") (name "unconnected-(U1-SDO{slash}SD0-Pad21)") (class "Default")
      (node (ref "U1") (pin "21") (pinfunction "SDO/SD0_21") (pintype "bidirectional"))
    )
    (net (code "73") (name "unconnected-(U1-SENSOR_VP-Pad4)") (class "Default")
      (node (ref "U1") (pin "4") (pinfunction "SENSOR_VP_4") (pintype "input"))
    )
    (net (code "74") (name "unconnected-(U1-SHD{slash}SD2-Pad17)") (class "Default")
      (node (ref "U1") (pin "17") (pinfunction "SHD/SD2_17") (pintype "bidirectional"))
    )
    (net (code "75") (name "unconnected-(U1-SWP{slash}SD3-Pad18)") (class "Default")
      (node (ref "U1") (pin "18") (pinfunction "SWP/SD3_18") (pintype "bidirectional"))
    )
    (net (code "76") (name "unconnected-(U3-NC.-Pad7)") (class "Default")
      (node (ref "U3") (pin "7") (pinfunction "NC._7") (pintype "no_connect"))
    )
    (net (code "77") (name "unconnected-(U3-R232-Pad15)") (class "Default")
      (node (ref "U3") (pin "15") (pinfunction "R232_15") (pintype "input"))
    )
    (net (code "78") (name "unconnected-(U3-~{CTS}-Pad9)") (class "Default")
      (node (ref "U3") (pin "9") (pinfunction "~{CTS}_9") (pintype "input"))
    )
    (net (code "79") (name "unconnected-(U3-~{DCD}-Pad12)") (class "Default")
      (node (ref "U3") (pin "12") (pinfunction "~{DCD}_12") (pintype "input"))
    )
    (net (code "80") (name "unconnected-(U3-~{DSR}-Pad10)") (class "Default")
      (node (ref "U3") (pin "10") (pinfunction "~{DSR}_10") (pintype "input"))
    )
    (net (code "81") (name "unconnected-(U3-~{OUT}-Pad8)") (class "Default")
      (node (ref "U3") (pin "8") (pinfunction "~{OUT}_8") (pintype "output"))
    )
    (net (code "82") (name "unconnected-(U3-~{RI}-Pad11)") (class "Default")
      (node (ref "U3") (pin "11") (pinfunction "~{RI}_11") (pintype "input"))
    )
  )
)
